# RF_Front.net
KiCad netlist of a schematic drawn in Altium Designer
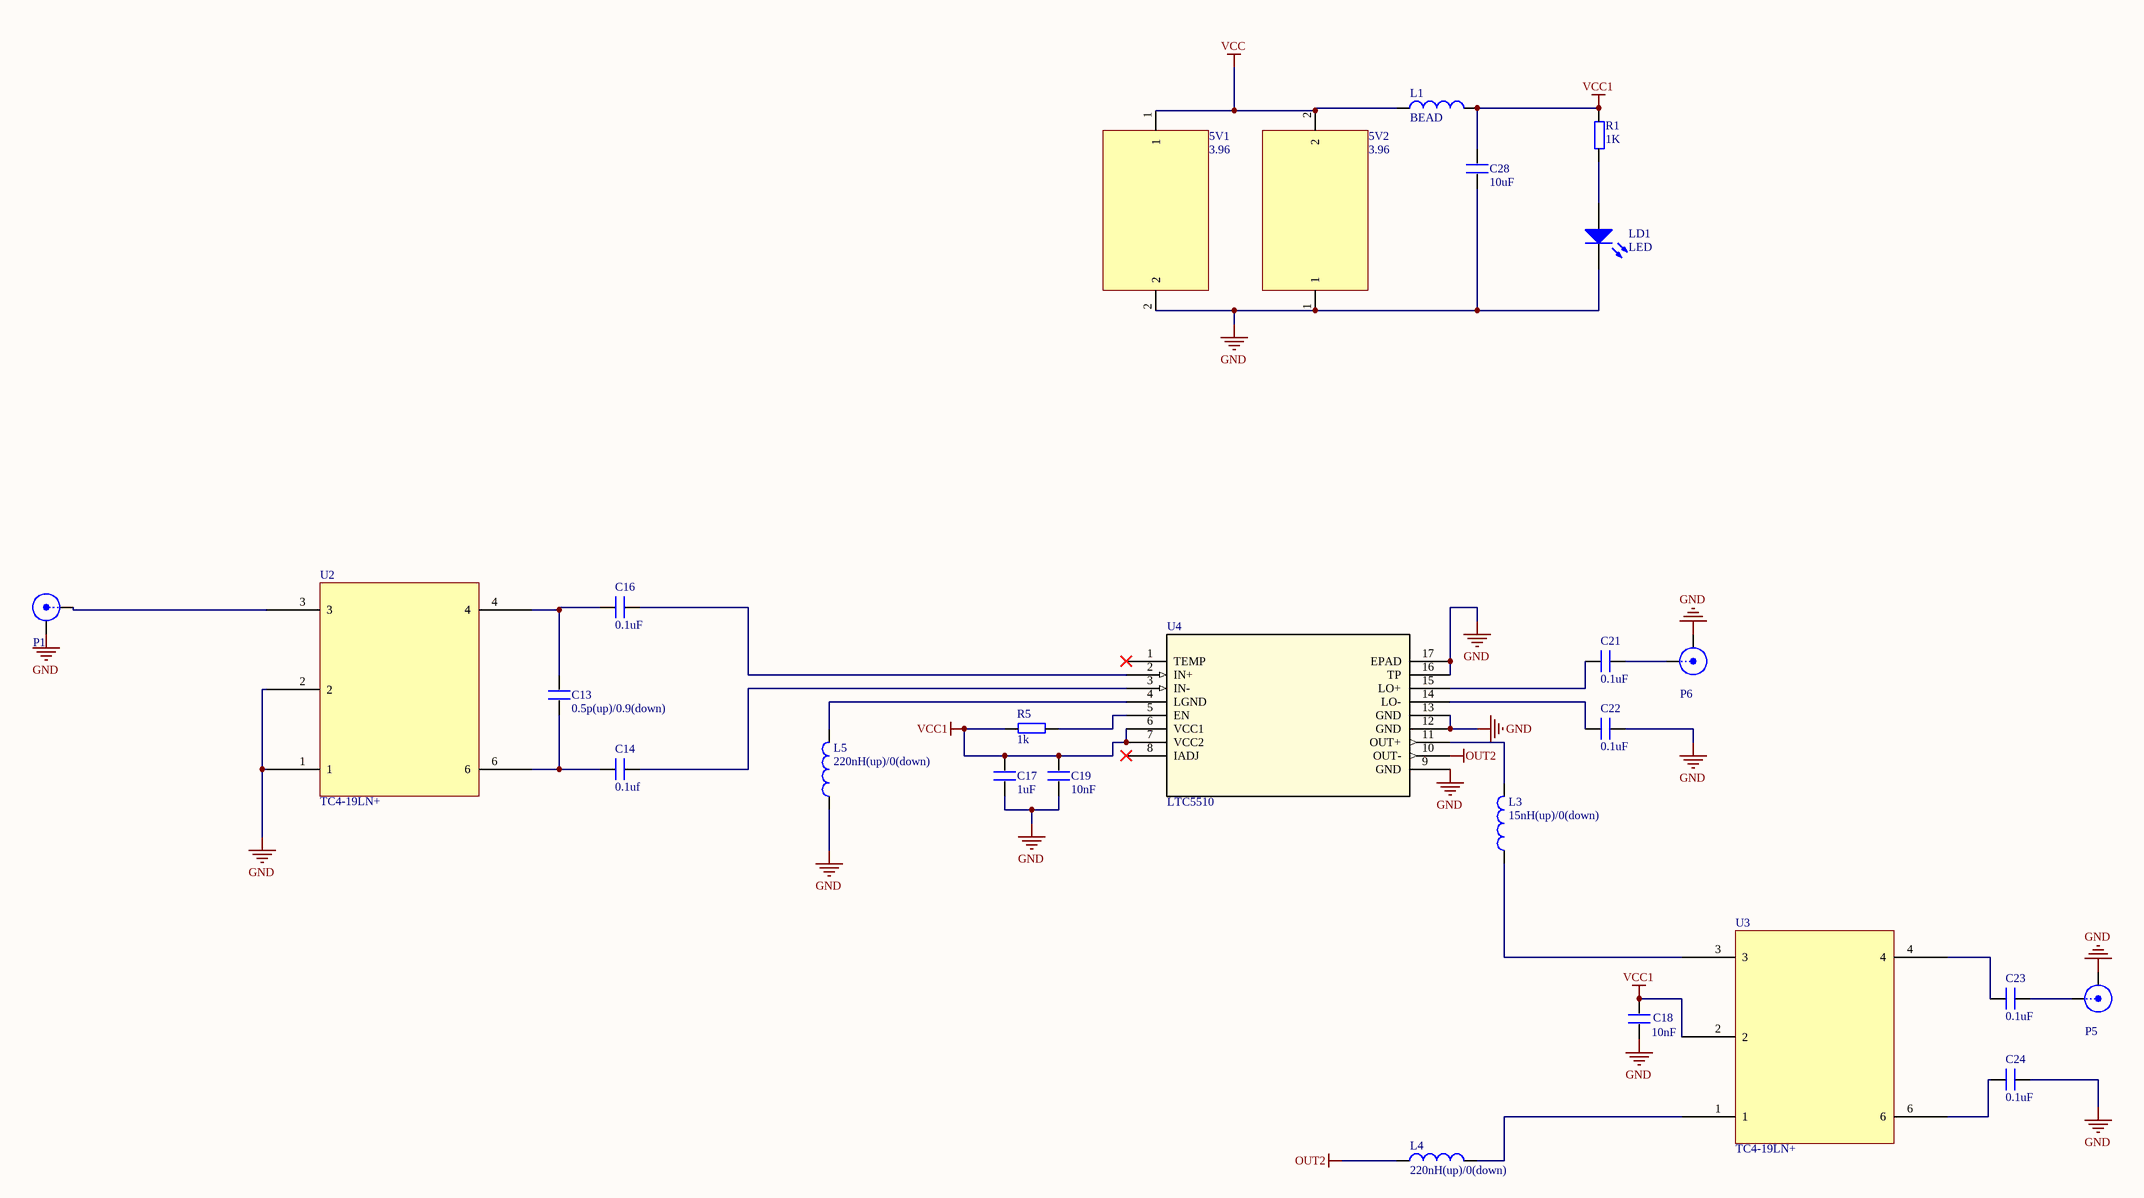
[diagram p0: RF Front.SchDoc]

(export (version "E")
  (design (tool "Eeschema 10.0.6"))
  (components
    (comp (ref "5V1") (value "3.96") (footprint "3.96") (libsource (lib "MYLIB") (part "3.96")))
    (comp (ref "5V2") (value "3.96") (footprint "3.96") (libsource (lib "") (part "3.96_1")))
    (comp (ref "C13")
      (value "0.5p(up)/0.9(down)")
      (footprint "0402")
      (description "Capacitor")
      (libsource (lib "MYLIB") (part "C"))
    )
    (comp (ref "C14")
      (value "0.1uf")
      (footprint "0402")
      (description "Capacitor")
      (libsource (lib "MYLIB") (part "C"))
    )
    (comp (ref "C16")
      (value "0.1uF")
      (footprint "0402")
      (description "Capacitor")
      (libsource (lib "MYLIB") (part "C"))
    )
    (comp (ref "C17")
      (value "1uF")
      (footprint "0402")
      (description "Capacitor")
      (libsource (lib "MYLIB") (part "C"))
    )
    (comp (ref "C18")
      (value "10nF")
      (footprint "0402")
      (description "Capacitor")
      (libsource (lib "MYLIB") (part "C"))
    )
    (comp (ref "C19")
      (value "10nF")
      (footprint "0402")
      (description "Capacitor")
      (libsource (lib "MYLIB") (part "C"))
    )
    (comp (ref "C21")
      (value "0.1uF")
      (footprint "0402")
      (description "Capacitor")
      (libsource (lib "MYLIB") (part "C"))
    )
    (comp (ref "C22")
      (value "0.1uF")
      (footprint "0402")
      (description "Capacitor")
      (libsource (lib "MYLIB") (part "C"))
    )
    (comp (ref "C23")
      (value "0.1uF")
      (footprint "0402")
      (description "Capacitor")
      (libsource (lib "MYLIB") (part "C"))
    )
    (comp (ref "C24")
      (value "0.1uF")
      (footprint "0402")
      (description "Capacitor")
      (libsource (lib "MYLIB") (part "C"))
    )
    (comp (ref "C28")
      (value "10uF")
      (footprint "0603C")
      (description "Capacitor")
      (libsource (lib "MYLIB") (part "C"))
    )
    (comp (ref "L1")
      (value "BEAD")
      (footprint "0603L")
      (description "Inductor")
      (fields (field (name "PUBLISHER") "Altium Limited"))
      (libsource (lib "MYLIB") (part "Inductor"))
    )
    (comp (ref "L3")
      (value "15nH(up)/0(down)")
      (footprint "0603L")
      (description "Inductor")
      (fields (field (name "PUBLISHER") "Altium Limited"))
      (libsource (lib "MYLIB") (part "Inductor"))
    )
    (comp (ref "L4")
      (value "220nH(up)/0(down)")
      (footprint "0603L")
      (description "Inductor")
      (fields (field (name "PUBLISHER") "Altium Limited"))
      (libsource (lib "MYLIB") (part "Inductor"))
    )
    (comp (ref "L5")
      (value "220nH(up)/0(down)")
      (footprint "0603L")
      (description "Inductor")
      (fields (field (name "PUBLISHER") "Altium Limited"))
      (libsource (lib "MYLIB") (part "Inductor"))
    )
    (comp (ref "LD1")
      (value "LED")
      (footprint "SMDLED")
      (description "Typical RED, GREEN, YELLOW, AMBER GaAs LED")
      (fields (field (name "PUBLISHER") "Altium Limited"))
      (libsource (lib "MYLIB") (part "LED"))
    )
    (comp (ref "P1")
      (value "SMA")
      (footprint "SMA")
      (description "SMA Connector")
      (libsource (lib "MYLIB") (part "SMA"))
    )
    (comp (ref "P5")
      (value "SMA")
      (footprint "SMA")
      (description "SMA Connector")
      (libsource (lib "MYLIB") (part "SMA"))
    )
    (comp (ref "P6")
      (value "SMA")
      (footprint "SMA")
      (description "SMA Connector")
      (libsource (lib "MYLIB") (part "SMA"))
    )
    (comp (ref "R1")
      (value "1K")
      (footprint "0603R")
      (description "Resistor")
      (libsource (lib "MYLIB") (part "Resistor"))
    )
    (comp (ref "R5")
      (value "1k")
      (footprint "0603R")
      (description "Resistor")
      (libsource (lib "MYLIB") (part "Resistor"))
    )
    (comp (ref "U2") (value "TC4-19LN+") (footprint "AT224") (libsource (lib "MYLIB") (part "TC4-19LN+")))
    (comp (ref "U3") (value "TC4-19LN+") (footprint "AT224") (libsource (lib "MYLIB") (part "TC4-19LN+")))
    (comp (ref "U4")
      (value "LTC5510")
      (footprint "QFN-16_UF")
      (description "1MHz 至 6GHz、宽带、高线性度有源混频器")
      (fields
        (field (name "MANUFACTURER_PART_NUMBER") "LTC5510IUF#TRPBF")
        (field (name "COPYRIGHT") "Copyright (C) 2018 Accelerated Designs. All rights reserved")
      )
      (libsource (lib "MYLIB") (part "LTC5510"))
    )
  )
  (nets
    (net (code "1") (name "GND") (class "Default")
      (node (ref "5V1") (pin "2") (pinfunction "2_2") (pintype "passive"))
      (node (ref "5V2") (pin "1") (pinfunction "1_1") (pintype "passive"))
      (node (ref "C17") (pin "2") (pintype "passive"))
      (node (ref "C18") (pin "1") (pintype "passive"))
      (node (ref "C19") (pin "2") (pintype "passive"))
      (node (ref "C22") (pin "2") (pintype "passive"))
      (node (ref "C24") (pin "2") (pintype "passive"))
      (node (ref "C28") (pin "1") (pintype "passive"))
      (node (ref "L5") (pin "1") (pinfunction "1_1") (pintype "passive"))
      (node (ref "LD1") (pin "2") (pinfunction "K_2") (pintype "passive"))
      (node (ref "P1") (pin "2") (pinfunction "Y_2") (pintype "passive"))
      (node (ref "P5") (pin "2") (pinfunction "Y_2") (pintype "passive"))
      (node (ref "P6") (pin "2") (pinfunction "Y_2") (pintype "passive"))
      (node (ref "U2") (pin "1") (pinfunction "1_1") (pintype "passive"))
      (node (ref "U2") (pin "2") (pinfunction "2_2") (pintype "passive"))
      (node (ref "U4") (pin "12") (pinfunction "GND_12") (pintype "power_in"))
      (node (ref "U4") (pin "13") (pinfunction "GND_13") (pintype "power_in"))
      (node (ref "U4") (pin "16") (pinfunction "TP_16") (pintype "passive"))
      (node (ref "U4") (pin "17") (pinfunction "EPAD_17") (pintype "passive"))
      (node (ref "U4") (pin "9") (pinfunction "GND_9") (pintype "power_in"))
    )
    (net (code "2") (name "Net-(C13-Pad1)") (class "Default")
      (node (ref "C13") (pin "1") (pintype "passive"))
      (node (ref "C14") (pin "2") (pintype "passive"))
      (node (ref "U2") (pin "6") (pinfunction "6_6") (pintype "passive"))
    )
    (net (code "3") (name "Net-(C13-Pad2)") (class "Default")
      (node (ref "C13") (pin "2") (pintype "passive"))
      (node (ref "C16") (pin "1") (pintype "passive"))
      (node (ref "U2") (pin "4") (pinfunction "4_4") (pintype "passive"))
    )
    (net (code "4") (name "Net-(C23-Pad1)") (class "Default")
      (node (ref "C23") (pin "1") (pintype "passive"))
      (node (ref "U3") (pin "4") (pinfunction "4_4") (pintype "passive"))
    )
    (net (code "5") (name "Net-(C24-Pad1)") (class "Default")
      (node (ref "C24") (pin "1") (pintype "passive"))
      (node (ref "U3") (pin "6") (pinfunction "6_6") (pintype "passive"))
    )
    (net (code "6") (name "Net-(L3-Pad1)") (class "Default")
      (node (ref "L3") (pin "1") (pinfunction "1_1") (pintype "passive"))
      (node (ref "U3") (pin "3") (pinfunction "3_3") (pintype "passive"))
    )
    (net (code "7") (name "Net-(L4-Pad2)") (class "Default")
      (node (ref "L4") (pin "2") (pinfunction "2_2") (pintype "passive"))
      (node (ref "U3") (pin "1") (pinfunction "1_1") (pintype "passive"))
    )
    (net (code "8") (name "Net-(LD1-A)") (class "Default")
      (node (ref "LD1") (pin "1") (pinfunction "A_1") (pintype "passive"))
      (node (ref "R1") (pin "1") (pintype "passive"))
    )
    (net (code "9") (name "Net-(P1-X)") (class "Default")
      (node (ref "P1") (pin "1") (pinfunction "X_1") (pintype "passive"))
      (node (ref "U2") (pin "3") (pinfunction "3_3") (pintype "passive"))
    )
    (net (code "10") (name "Net-(P5-X)") (class "Default")
      (node (ref "C23") (pin "2") (pintype "passive"))
      (node (ref "P5") (pin "1") (pinfunction "X_1") (pintype "passive"))
    )
    (net (code "11") (name "Net-(P6-X)") (class "Default")
      (node (ref "C21") (pin "1") (pintype "passive"))
      (node (ref "P6") (pin "1") (pinfunction "X_1") (pintype "passive"))
    )
    (net (code "12") (name "Net-(U4-EN)") (class "Default")
      (node (ref "R5") (pin "1") (pintype "passive"))
      (node (ref "U4") (pin "5") (pinfunction "EN_5") (pintype "passive"))
    )
    (net (code "13") (name "Net-(U4-IN+)") (class "Default")
      (node (ref "C16") (pin "2") (pintype "passive"))
      (node (ref "U4") (pin "2") (pinfunction "IN+_2") (pintype "input"))
    )
    (net (code "14") (name "Net-(U4-IN-)") (class "Default")
      (node (ref "C14") (pin "1") (pintype "passive"))
      (node (ref "U4") (pin "3") (pinfunction "IN-_3") (pintype "input"))
    )
    (net (code "15") (name "Net-(U4-LGND)") (class "Default")
      (node (ref "L5") (pin "2") (pinfunction "2_2") (pintype "passive"))
      (node (ref "U4") (pin "4") (pinfunction "LGND_4") (pintype "power_in"))
    )
    (net (code "16") (name "Net-(U4-LO+)") (class "Default")
      (node (ref "C21") (pin "2") (pintype "passive"))
      (node (ref "U4") (pin "15") (pinfunction "LO+_15") (pintype "passive"))
    )
    (net (code "17") (name "Net-(U4-LO-)") (class "Default")
      (node (ref "C22") (pin "1") (pintype "passive"))
      (node (ref "U4") (pin "14") (pinfunction "LO-_14") (pintype "passive"))
    )
    (net (code "18") (name "Net-(U4-OUT+)") (class "Default")
      (node (ref "L3") (pin "2") (pinfunction "2_2") (pintype "passive"))
      (node (ref "U4") (pin "11") (pinfunction "OUT+_11") (pintype "output"))
    )
    (net (code "19") (name "OUT2") (class "Default")
      (node (ref "L4") (pin "1") (pinfunction "1_1") (pintype "passive"))
      (node (ref "U4") (pin "10") (pinfunction "OUT-_10") (pintype "output"))
    )
    (net (code "20") (name "VCC") (class "Default")
      (node (ref "5V1") (pin "1") (pinfunction "1_1") (pintype "passive"))
      (node (ref "5V2") (pin "2") (pinfunction "2_2") (pintype "passive"))
      (node (ref "L1") (pin "1") (pinfunction "1_1") (pintype "passive"))
    )
    (net (code "21") (name "VCC1") (class "Default")
      (node (ref "C17") (pin "1") (pintype "passive"))
      (node (ref "C18") (pin "2") (pintype "passive"))
      (node (ref "C19") (pin "1") (pintype "passive"))
      (node (ref "C28") (pin "2") (pintype "passive"))
      (node (ref "L1") (pin "2") (pinfunction "2_2") (pintype "passive"))
      (node (ref "R1") (pin "2") (pintype "passive"))
      (node (ref "R5") (pin "2") (pintype "passive"))
      (node (ref "U3") (pin "2") (pinfunction "2_2") (pintype "passive"))
      (node (ref "U4") (pin "6") (pinfunction "VCC1_6") (pintype "power_in"))
      (node (ref "U4") (pin "7") (pinfunction "VCC2_7") (pintype "power_in"))
    )
    (net (code "22") (name "unconnected-(U4-IADJ-Pad8)") (class "Default")
      (node (ref "U4") (pin "8") (pinfunction "IADJ_8") (pintype "passive+no_connect"))
    )
    (net (code "23") (name "unconnected-(U4-TEMP-Pad1)") (class "Default")
      (node (ref "U4") (pin "1") (pinfunction "TEMP_1") (pintype "passive+no_connect"))
    )
  )
)
